# NCP177.net
KiCad netlist of a schematic drawn in Altium Designer
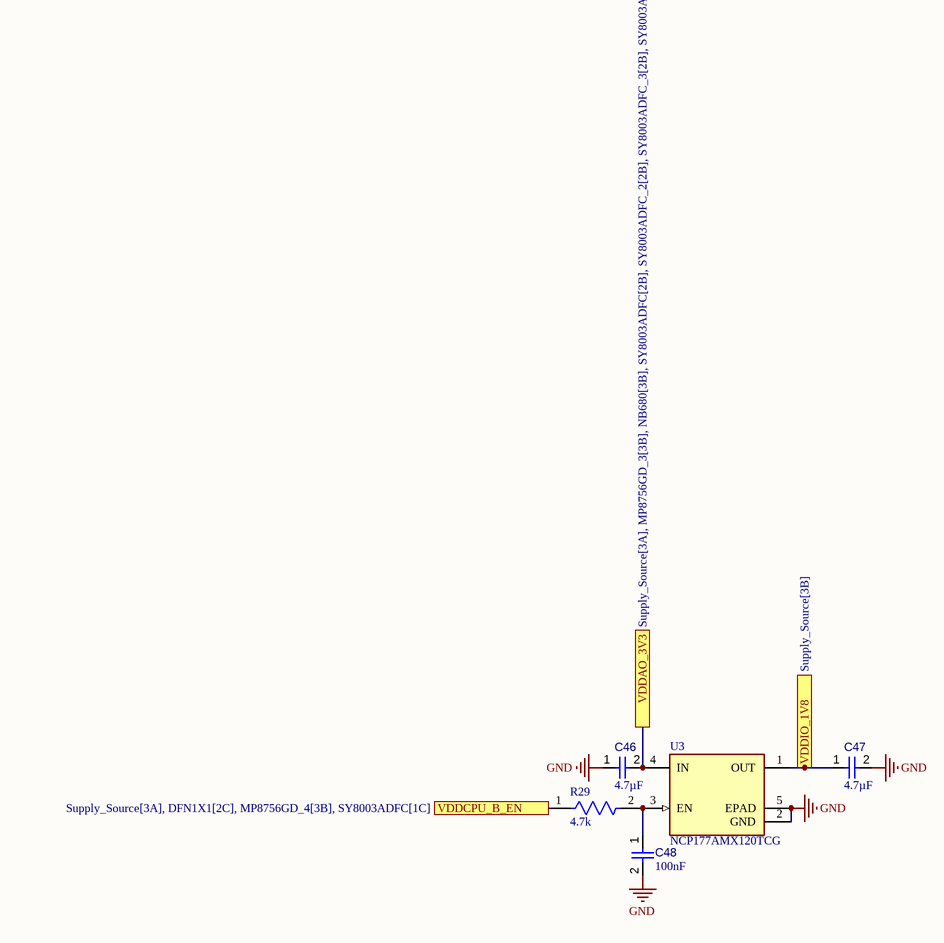
[diagram p0: NCP177.SchDoc]

(export (version "E")
  (design (tool "Eeschema 10.0.6"))
  (components
    (comp (ref "C46")
      (value "4.7µF")
      (footprint "CAPC0603(1608)100_L")
      (description "Chip Capacitor, 4.7µF +/-20%, 10V, 0603, Thickness 1 mm")
      (fields (field (name "TOLERANCE") "10%") (field (name "Comment") "Capacitor 4.7µF +/-20% 10V 0603"))
      (libsource (lib "MIGUEL ANGEL ALVAREZ GUZMAN") (part "CAP-NP-2"))
    )
    (comp (ref "C47")
      (value "4.7µF")
      (footprint "CAPC0603(1608)100_L")
      (description "Chip Capacitor, 4.7µF +/-20%, 10V, 0603, Thickness 1 mm")
      (fields (field (name "TOLERANCE") "10%") (field (name "Comment") "Capacitor 4.7µF +/-20% 10V 0603"))
      (libsource (lib "MIGUEL ANGEL ALVAREZ GUZMAN") (part "CAP-NP-2"))
    )
    (comp (ref "C48")
      (value "100nF")
      (footprint "CAPC1005X56X25LL10T15")
      (description "Chip Capacitor, 0.1 uF, +/- 5%, 16 V, 0402 (1005 Metric)")
      (fields (field (name "TOLERANCE") "5%") (field (name "Comment") "Capacitor 0.1 uF +/- 5% 16 V 0402"))
      (libsource (lib "MIGUEL ANGEL ALVAREZ GUZMAN") (part "CAP-NP-2"))
    )
    (comp (ref "R29")
      (value "4.7k")
      (footprint "FP-RMCF0201-IPC_A")
      (description "Res Thick Film 0201 4.7K Ohm 5% 0.05W(1/20W) ±200ppm/C Pad SMD Automotive T/R")
      (fields (field (name "TOLERANCE") "5%") (field (name "Comment") "RMCF0201JT4K70"))
      (libsource (lib "MIGUEL ANGEL ALVAREZ GUZMAN") (part "1029c3af85768c4190bb7ad29bc67b5"))
    )
    (comp (ref "U3")
      (value "NCP177AMX120TCG")
      (footprint "FP-711AJ-MFG")
      (description "IC REG LINEAR 1.2V 500MA 4XDFN")
      (fields
        (field (name "OCTOPART") "https://octopart.com/ncp177amx120tcg-on+semiconductor-67320276")
        (field (name "MANUFACTURER") "ON Semiconductor")
      )
      (libsource (lib "Altium Content Vault") (part "8ad8dfd97c3e3b1b30caf0b800727eb"))
    )
  )
  (nets
    (net (code "1") (name "/VDDAO_3V3") (class "Default")
      (node (ref "C46") (pin "2") (pinfunction "2_2") (pintype "passive"))
      (node (ref "U3") (pin "4") (pinfunction "IN_4") (pintype "power_in"))
    )
    (net (code "2") (name "/VDDCPU_B_EN") (class "Default")
      (node (ref "R29") (pin "1") (pinfunction "1_1") (pintype "passive"))
    )
    (net (code "3") (name "/VDDIO_1V8") (class "Default")
      (node (ref "C47") (pin "1") (pinfunction "1_1") (pintype "passive"))
      (node (ref "U3") (pin "1") (pinfunction "OUT_1") (pintype "power_in"))
    )
    (net (code "4") (name "GND") (class "Default")
      (node (ref "C46") (pin "1") (pinfunction "1_1") (pintype "passive"))
      (node (ref "C47") (pin "2") (pinfunction "2_2") (pintype "passive"))
      (node (ref "C48") (pin "2") (pinfunction "2_2") (pintype "passive"))
      (node (ref "U3") (pin "2") (pinfunction "GND_2") (pintype "power_in"))
      (node (ref "U3") (pin "5") (pinfunction "EPAD_5") (pintype "power_in"))
    )
    (net (code "5") (name "Net-(U3-EN)") (class "Default")
      (node (ref "C48") (pin "1") (pinfunction "1_1") (pintype "passive"))
      (node (ref "R29") (pin "2") (pinfunction "2_2") (pintype "passive"))
      (node (ref "U3") (pin "3") (pinfunction "EN_3") (pintype "input"))
    )
  )
)
